# PogoBoard.net
KiCad netlist of a schematic drawn in EAGLE
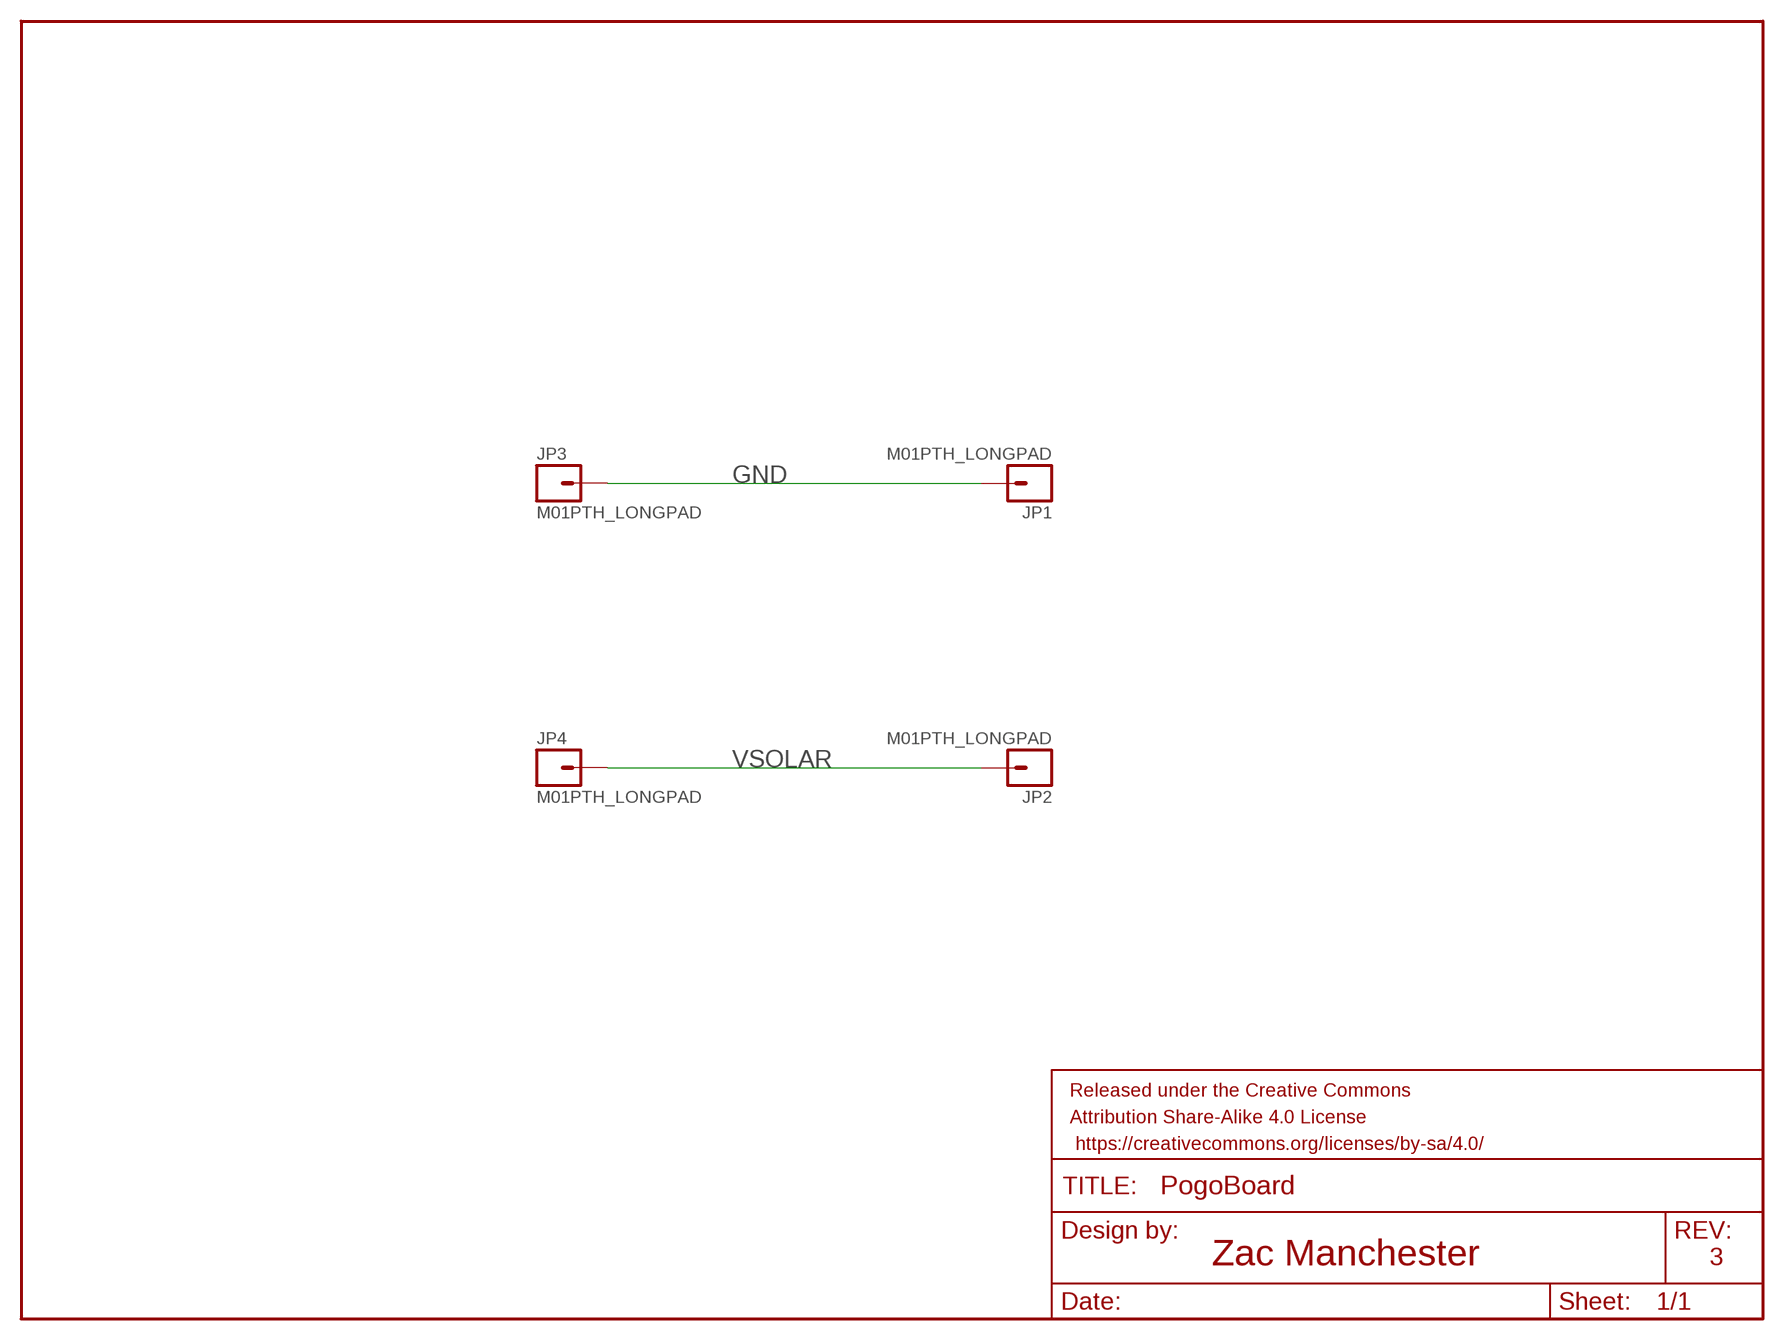
[diagram p0: schematic, sheet 1]

(export (version "E")
  (design (tool "Eeschema 10.0.6"))
  (components
    (comp (ref "FRAME1")
      (value "FRAME-LETTER")
      (footprint "eagle-import:CREATIVE_COMMONS")
      (libsource (lib "eagle-import") (part "FRAME-LETTER"))
    )
    (comp (ref "JP1")
      (value "M01PTH_LONGPAD")
      (footprint "eagle-import:1X01_LONGPAD")
      (libsource (lib "eagle-import") (part "M01PTH_LONGPAD"))
    )
    (comp (ref "JP2")
      (value "M01PTH_LONGPAD")
      (footprint "eagle-import:1X01_LONGPAD")
      (libsource (lib "eagle-import") (part "M01PTH_LONGPAD"))
    )
    (comp (ref "JP3")
      (value "M01PTH_LONGPAD")
      (footprint "eagle-import:1X01_LONGPAD")
      (libsource (lib "eagle-import") (part "M01PTH_LONGPAD"))
    )
    (comp (ref "JP4")
      (value "M01PTH_LONGPAD")
      (footprint "eagle-import:1X01_LONGPAD")
      (libsource (lib "eagle-import") (part "M01PTH_LONGPAD"))
    )
  )
  (nets
    (net (code "1") (name "/GND") (class "Default")
      (node (ref "JP1") (pin "1") (pinfunction "1_1") (pintype "passive"))
      (node (ref "JP3") (pin "1") (pinfunction "1_1") (pintype "passive"))
    )
    (net (code "2") (name "/VSOLAR") (class "Default")
      (node (ref "JP2") (pin "1") (pinfunction "1_1") (pintype "passive"))
      (node (ref "JP4") (pin "1") (pinfunction "1_1") (pintype "passive"))
    )
  )
)
